# v1sch.net
KiCad netlist of a schematic drawn in EAGLE
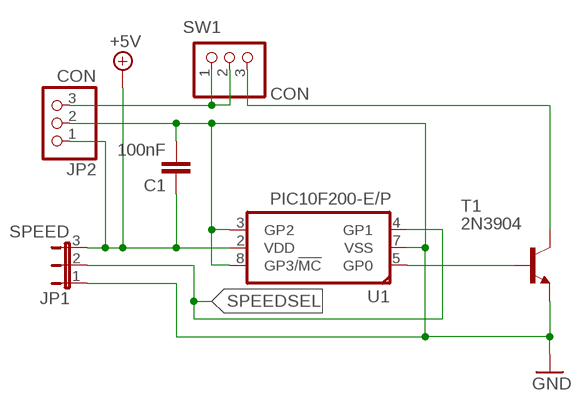
[diagram p0: schematic, sheet 1]

(export (version "E")
  (design (tool "Eeschema 10.0.6"))
  (components
    (comp (ref "C1")
      (value "100nF")
      (footprint "eagle-import:C025-025X050")
      (libsource (lib "eagle-import") (part "C-EU025-025X050"))
    )
    (comp (ref "JP1")
      (value "SPEED")
      (footprint "eagle-import:JP2")
      (libsource (lib "eagle-import") (part "JP2E"))
    )
    (comp (ref "JP2")
      (value "CON")
      (footprint "eagle-import:1X03")
      (libsource (lib "eagle-import") (part "PINHD-1X3"))
    )
    (comp (ref "SW1")
      (value "CON")
      (footprint "eagle-import:1X03")
      (libsource (lib "eagle-import") (part "PINHD-1X3"))
    )
    (comp (ref "T1")
      (value "2N3904")
      (footprint "eagle-import:TO92")
      (fields (field (name "MF") "MULTICOMP"))
      (libsource (lib "eagle-import") (part "2N3904"))
    )
    (comp (ref "U1")
      (value "PIC10F200-E/P")
      (footprint "eagle-import:DIL08")
      (libsource (lib "eagle-import") (part "PIC10F200P"))
    )
  )
  (nets
    (net (code "1") (name "+5V") (class "Default")
      (node (ref "C1") (pin "1") (pinfunction "1_1") (pintype "passive"))
      (node (ref "JP1") (pin "3") (pinfunction "3_3") (pintype "passive"))
      (node (ref "JP2") (pin "1") (pinfunction "1_1") (pintype "passive"))
      (node (ref "U1") (pin "2") (pinfunction "VDD_2") (pintype "passive"))
    )
    (net (code "2") (name "GND") (class "Default")
      (node (ref "C1") (pin "2") (pinfunction "2_2") (pintype "passive"))
      (node (ref "JP1") (pin "1") (pinfunction "1_1") (pintype "passive"))
      (node (ref "JP2") (pin "2") (pinfunction "2_2") (pintype "passive"))
      (node (ref "T1") (pin "3") (pinfunction "E_3") (pintype "passive"))
      (node (ref "U1") (pin "3") (pinfunction "GP2_3") (pintype "bidirectional"))
      (node (ref "U1") (pin "7") (pinfunction "VSS_7") (pintype "passive"))
      (node (ref "U1") (pin "8") (pinfunction "GP3/~{MC}_8") (pintype "input"))
    )
    (net (code "3") (name "Net-(JP2-Pad3)") (class "Default")
      (node (ref "JP2") (pin "3") (pinfunction "3_3") (pintype "passive"))
      (node (ref "SW1") (pin "1") (pinfunction "1_1") (pintype "passive"))
      (node (ref "SW1") (pin "2") (pinfunction "2_2") (pintype "passive"))
    )
    (net (code "4") (name "Net-(T1-B)") (class "Default")
      (node (ref "T1") (pin "2") (pinfunction "B_2") (pintype "passive"))
      (node (ref "U1") (pin "5") (pinfunction "GP0_5") (pintype "bidirectional"))
    )
    (net (code "5") (name "Net-(T1-C)") (class "Default")
      (node (ref "SW1") (pin "3") (pinfunction "3_3") (pintype "passive"))
      (node (ref "T1") (pin "1") (pinfunction "C_1") (pintype "passive"))
    )
    (net (code "6") (name "SPEEDSEL") (class "Default")
      (node (ref "JP1") (pin "2") (pinfunction "2_2") (pintype "passive"))
      (node (ref "U1") (pin "4") (pinfunction "GP1_4") (pintype "bidirectional"))
    )
  )
)
